# fancontrol.net
KiCad netlist of a schematic drawn in EAGLE
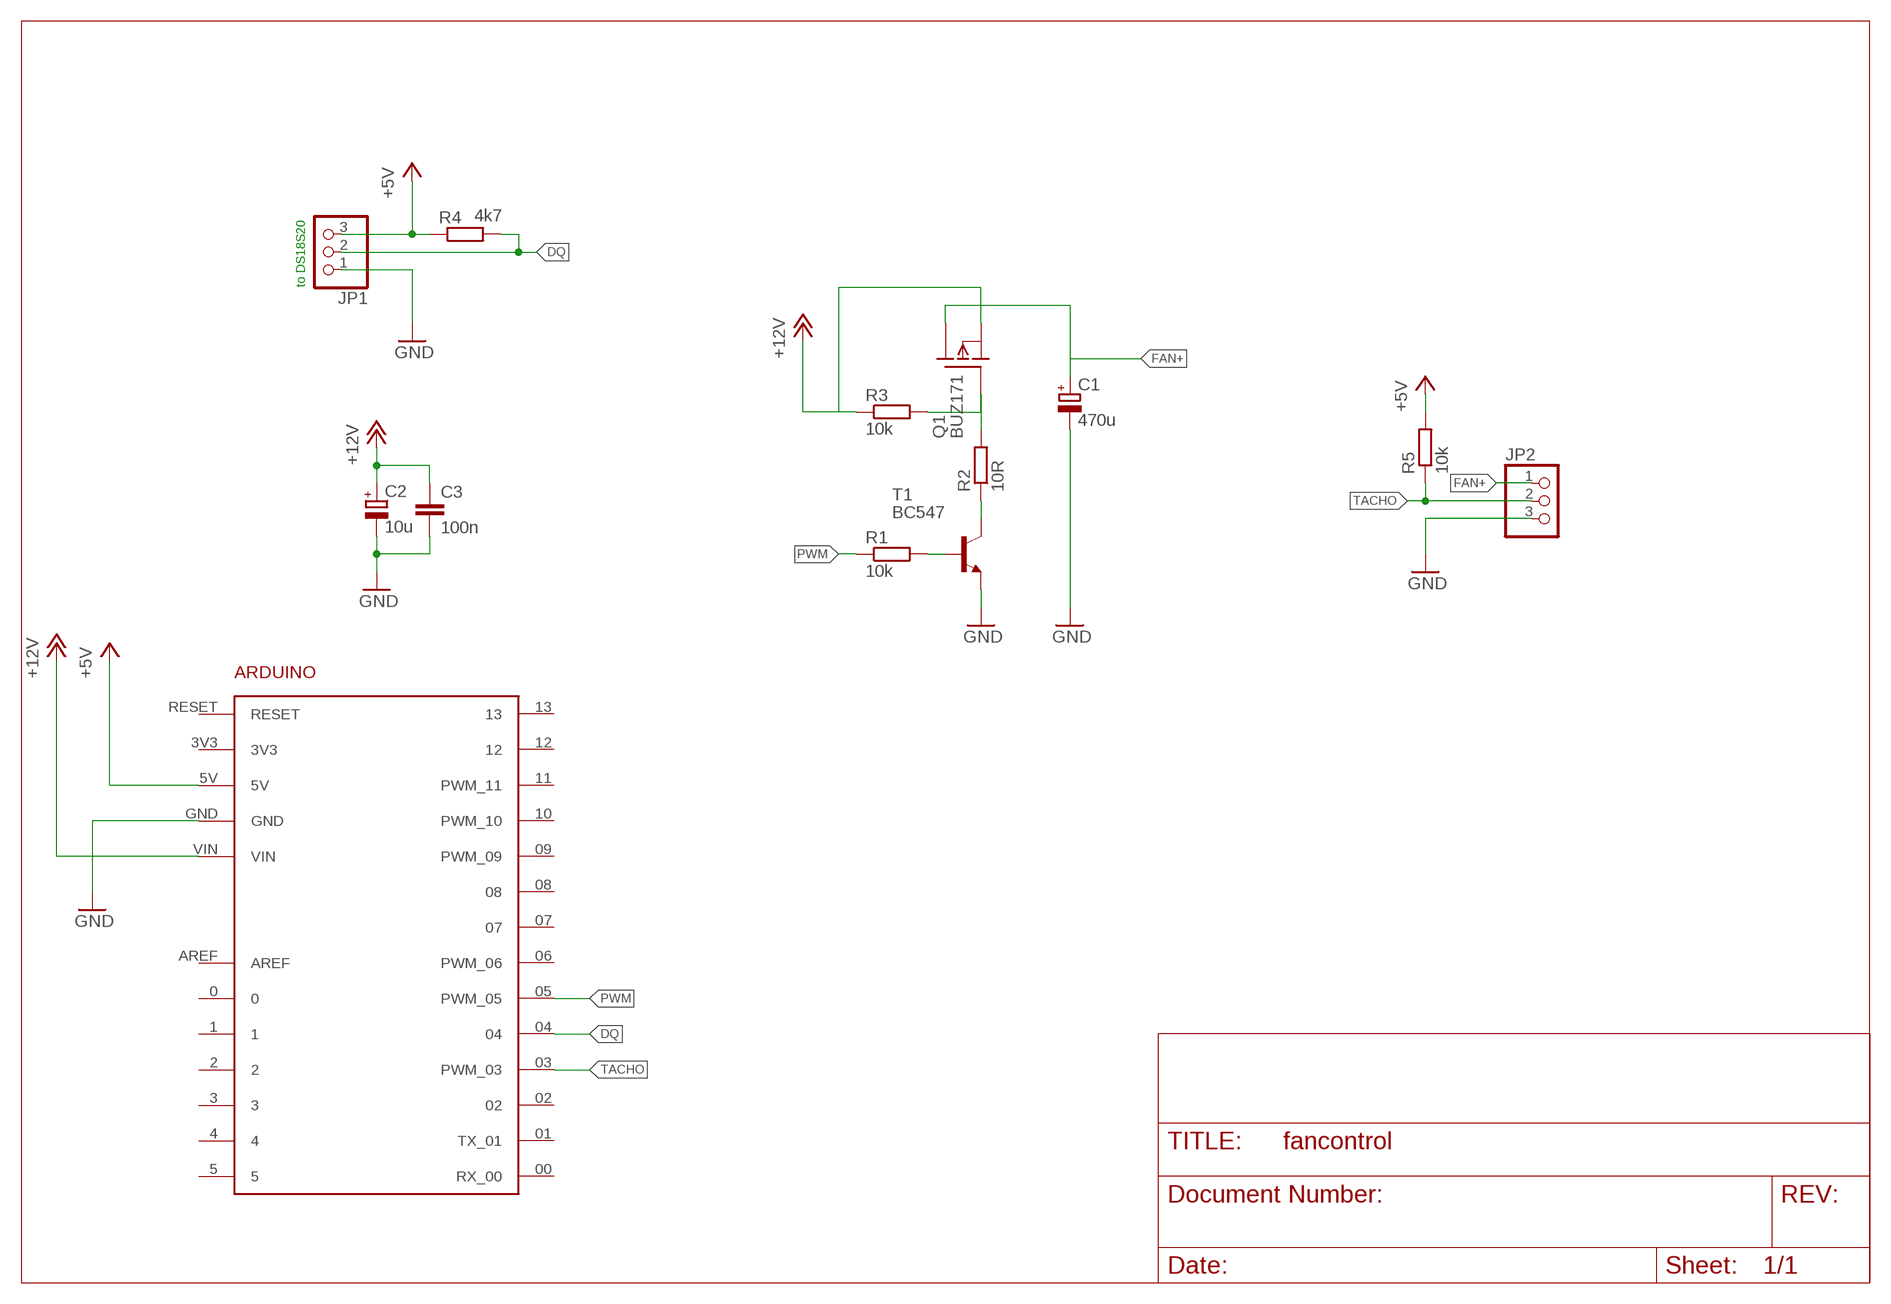
[diagram p0: schematic, sheet 1]

(export (version "E")
  (design (tool "Eeschema 10.0.6"))
  (components
    (comp (ref "ARDUINO1")
      (value "ARDUINO")
      (footprint "eagle-import:ARDUINO")
      (libsource (lib "eagle-import") (part "ARDUINO"))
    )
    (comp (ref "C1")
      (value "470u")
      (footprint "eagle-import:E5-10,5")
      (libsource (lib "eagle-import") (part "CPOL-EUE5-10.5"))
    )
    (comp (ref "C2")
      (value "10u")
      (footprint "eagle-import:E2,5-5")
      (libsource (lib "eagle-import") (part "CPOL-EUE2.5-5"))
    )
    (comp (ref "C3")
      (value "100n")
      (footprint "eagle-import:C025-025X050")
      (libsource (lib "eagle-import") (part "C-EU025-025X050"))
    )
    (comp (ref "JP1")
      (value "PINHD-1X3")
      (footprint "eagle-import:1X03")
      (libsource (lib "eagle-import") (part "PINHD-1X3"))
    )
    (comp (ref "JP2")
      (value "PINHD-1X3")
      (footprint "eagle-import:1X03")
      (libsource (lib "eagle-import") (part "PINHD-1X3"))
    )
    (comp (ref "Q1")
      (value "BUZ171")
      (footprint "eagle-import:TO220")
      (libsource (lib "eagle-import") (part "BUZ171"))
    )
    (comp (ref "R1")
      (value "10k")
      (footprint "eagle-import:0207_7")
      (libsource (lib "eagle-import") (part "R-EU_0207/7"))
    )
    (comp (ref "R2")
      (value "10R")
      (footprint "eagle-import:0207_7")
      (libsource (lib "eagle-import") (part "R-EU_0207/7"))
    )
    (comp (ref "R3")
      (value "10k")
      (footprint "eagle-import:0207_7")
      (libsource (lib "eagle-import") (part "R-EU_0207/7"))
    )
    (comp (ref "R4")
      (value "4k7")
      (footprint "eagle-import:0207_7")
      (libsource (lib "eagle-import") (part "R-EU_0207/7"))
    )
    (comp (ref "R5")
      (value "10k")
      (footprint "eagle-import:0207_7")
      (libsource (lib "eagle-import") (part "R-EU_0207/7"))
    )
    (comp (ref "T1")
      (value "BC547")
      (footprint "eagle-import:TO92")
      (libsource (lib "eagle-import") (part "BC547"))
    )
  )
  (nets
    (net (code "1") (name "+5V") (class "Default")
      (node (ref "ARDUINO1") (pin "5V") (pinfunction "5V_5V") (pintype "bidirectional"))
      (node (ref "JP1") (pin "3") (pinfunction "3_3") (pintype "passive"))
      (node (ref "R4") (pin "1") (pinfunction "1_1") (pintype "passive"))
      (node (ref "R5") (pin "2") (pinfunction "2_2") (pintype "passive"))
    )
    (net (code "2") (name "+12V") (class "Default")
      (node (ref "ARDUINO1") (pin "VIN") (pinfunction "VIN_VIN") (pintype "bidirectional"))
      (node (ref "C2") (pin "+") (pinfunction "+_+") (pintype "passive"))
      (node (ref "C3") (pin "1") (pinfunction "1_1") (pintype "passive"))
      (node (ref "Q1") (pin "3") (pinfunction "S_3") (pintype "passive"))
      (node (ref "R3") (pin "1") (pinfunction "1_1") (pintype "passive"))
    )
    (net (code "3") (name "DQ") (class "Default")
      (node (ref "ARDUINO1") (pin "04") (pinfunction "04_04") (pintype "bidirectional"))
      (node (ref "JP1") (pin "2") (pinfunction "2_2") (pintype "passive"))
      (node (ref "R4") (pin "2") (pinfunction "2_2") (pintype "passive"))
    )
    (net (code "4") (name "FAN+") (class "Default")
      (node (ref "C1") (pin "+") (pinfunction "+_+") (pintype "passive"))
      (node (ref "JP2") (pin "1") (pinfunction "1_1") (pintype "passive"))
      (node (ref "Q1") (pin "2") (pinfunction "D_2") (pintype "passive"))
    )
    (net (code "5") (name "GND") (class "Default")
      (node (ref "ARDUINO1") (pin "GND") (pinfunction "GND_GND") (pintype "bidirectional"))
      (node (ref "C1") (pin "-") (pinfunction "-_-") (pintype "passive"))
      (node (ref "C2") (pin "-") (pinfunction "-_-") (pintype "passive"))
      (node (ref "C3") (pin "2") (pinfunction "2_2") (pintype "passive"))
      (node (ref "JP1") (pin "1") (pinfunction "1_1") (pintype "passive"))
      (node (ref "JP2") (pin "3") (pinfunction "3_3") (pintype "passive"))
      (node (ref "T1") (pin "1") (pinfunction "E_1") (pintype "passive"))
    )
    (net (code "6") (name "Net-(Q1-G)") (class "Default")
      (node (ref "Q1") (pin "1") (pinfunction "G_1") (pintype "passive"))
      (node (ref "R2") (pin "2") (pinfunction "2_2") (pintype "passive"))
      (node (ref "R3") (pin "2") (pinfunction "2_2") (pintype "passive"))
    )
    (net (code "7") (name "Net-(T1-B)") (class "Default")
      (node (ref "R1") (pin "2") (pinfunction "2_2") (pintype "passive"))
      (node (ref "T1") (pin "2") (pinfunction "B_2") (pintype "passive"))
    )
    (net (code "8") (name "Net-(T1-C)") (class "Default")
      (node (ref "R2") (pin "1") (pinfunction "1_1") (pintype "passive"))
      (node (ref "T1") (pin "3") (pinfunction "C_3") (pintype "passive"))
    )
    (net (code "9") (name "PWM") (class "Default")
      (node (ref "ARDUINO1") (pin "05") (pinfunction "PWM_05_05") (pintype "bidirectional"))
      (node (ref "R1") (pin "1") (pinfunction "1_1") (pintype "passive"))
    )
    (net (code "10") (name "TACHO") (class "Default")
      (node (ref "ARDUINO1") (pin "03") (pinfunction "PWM_03_03") (pintype "bidirectional"))
      (node (ref "JP2") (pin "2") (pinfunction "2_2") (pintype "passive"))
      (node (ref "R5") (pin "1") (pinfunction "1_1") (pintype "passive"))
    )
    (net (code "11") (name "unconnected-(ARDUINO1-PWM_06-Pad06)") (class "Default")
      (node (ref "ARDUINO1") (pin "06") (pinfunction "PWM_06_06") (pintype "bidirectional"))
    )
    (net (code "12") (name "unconnected-(ARDUINO1-PWM_09-Pad09)") (class "Default")
      (node (ref "ARDUINO1") (pin "09") (pinfunction "PWM_09_09") (pintype "bidirectional"))
    )
    (net (code "13") (name "unconnected-(ARDUINO1-PWM_10-Pad10)") (class "Default")
      (node (ref "ARDUINO1") (pin "10") (pinfunction "PWM_10_10") (pintype "bidirectional"))
    )
    (net (code "14") (name "unconnected-(ARDUINO1-PWM_11-Pad11)") (class "Default")
      (node (ref "ARDUINO1") (pin "11") (pinfunction "PWM_11_11") (pintype "bidirectional"))
    )
    (net (code "15") (name "unconnected-(ARDUINO1-Pad0)") (class "Default")
      (node (ref "ARDUINO1") (pin "0") (pinfunction "0_0") (pintype "bidirectional"))
    )
    (net (code "16") (name "unconnected-(ARDUINO1-Pad1)") (class "Default")
      (node (ref "ARDUINO1") (pin "1") (pinfunction "1_1") (pintype "bidirectional"))
    )
    (net (code "17") (name "unconnected-(ARDUINO1-Pad02)") (class "Default")
      (node (ref "ARDUINO1") (pin "02") (pinfunction "02_02") (pintype "bidirectional"))
    )
    (net (code "18") (name "unconnected-(ARDUINO1-Pad2)") (class "Default")
      (node (ref "ARDUINO1") (pin "2") (pinfunction "2_2") (pintype "bidirectional"))
    )
    (net (code "19") (name "unconnected-(ARDUINO1-Pad3)") (class "Default")
      (node (ref "ARDUINO1") (pin "3") (pinfunction "3_3") (pintype "bidirectional"))
    )
    (net (code "20") (name "unconnected-(ARDUINO1-Pad3V3)") (class "Default")
      (node (ref "ARDUINO1") (pin "3V3") (pinfunction "3V3_3V3") (pintype "bidirectional"))
    )
    (net (code "21") (name "unconnected-(ARDUINO1-Pad4)") (class "Default")
      (node (ref "ARDUINO1") (pin "4") (pinfunction "4_4") (pintype "bidirectional"))
    )
    (net (code "22") (name "unconnected-(ARDUINO1-Pad5)") (class "Default")
      (node (ref "ARDUINO1") (pin "5") (pinfunction "5_5") (pintype "bidirectional"))
    )
    (net (code "23") (name "unconnected-(ARDUINO1-Pad07)") (class "Default")
      (node (ref "ARDUINO1") (pin "07") (pinfunction "07_07") (pintype "bidirectional"))
    )
    (net (code "24") (name "unconnected-(ARDUINO1-Pad08)") (class "Default")
      (node (ref "ARDUINO1") (pin "08") (pinfunction "08_08") (pintype "bidirectional"))
    )
    (net (code "25") (name "unconnected-(ARDUINO1-Pad12)") (class "Default")
      (node (ref "ARDUINO1") (pin "12") (pinfunction "12_12") (pintype "bidirectional"))
    )
    (net (code "26") (name "unconnected-(ARDUINO1-Pad13)") (class "Default")
      (node (ref "ARDUINO1") (pin "13") (pinfunction "13_13") (pintype "bidirectional"))
    )
    (net (code "27") (name "unconnected-(ARDUINO1-PadAREF)") (class "Default")
      (node (ref "ARDUINO1") (pin "AREF") (pinfunction "AREF_AREF") (pintype "bidirectional"))
    )
    (net (code "28") (name "unconnected-(ARDUINO1-PadRESET)") (class "Default")
      (node (ref "ARDUINO1") (pin "RESET") (pinfunction "RESET_RESET") (pintype "bidirectional"))
    )
    (net (code "29") (name "unconnected-(ARDUINO1-RX_00-Pad00)") (class "Default")
      (node (ref "ARDUINO1") (pin "00") (pinfunction "RX_00_00") (pintype "bidirectional"))
    )
    (net (code "30") (name "unconnected-(ARDUINO1-TX_01-Pad01)") (class "Default")
      (node (ref "ARDUINO1") (pin "01") (pinfunction "TX_01_01") (pintype "bidirectional"))
    )
  )
)
